# SparkFun_GPS_ZED-F9K.net
KiCad netlist of a schematic drawn in EAGLE
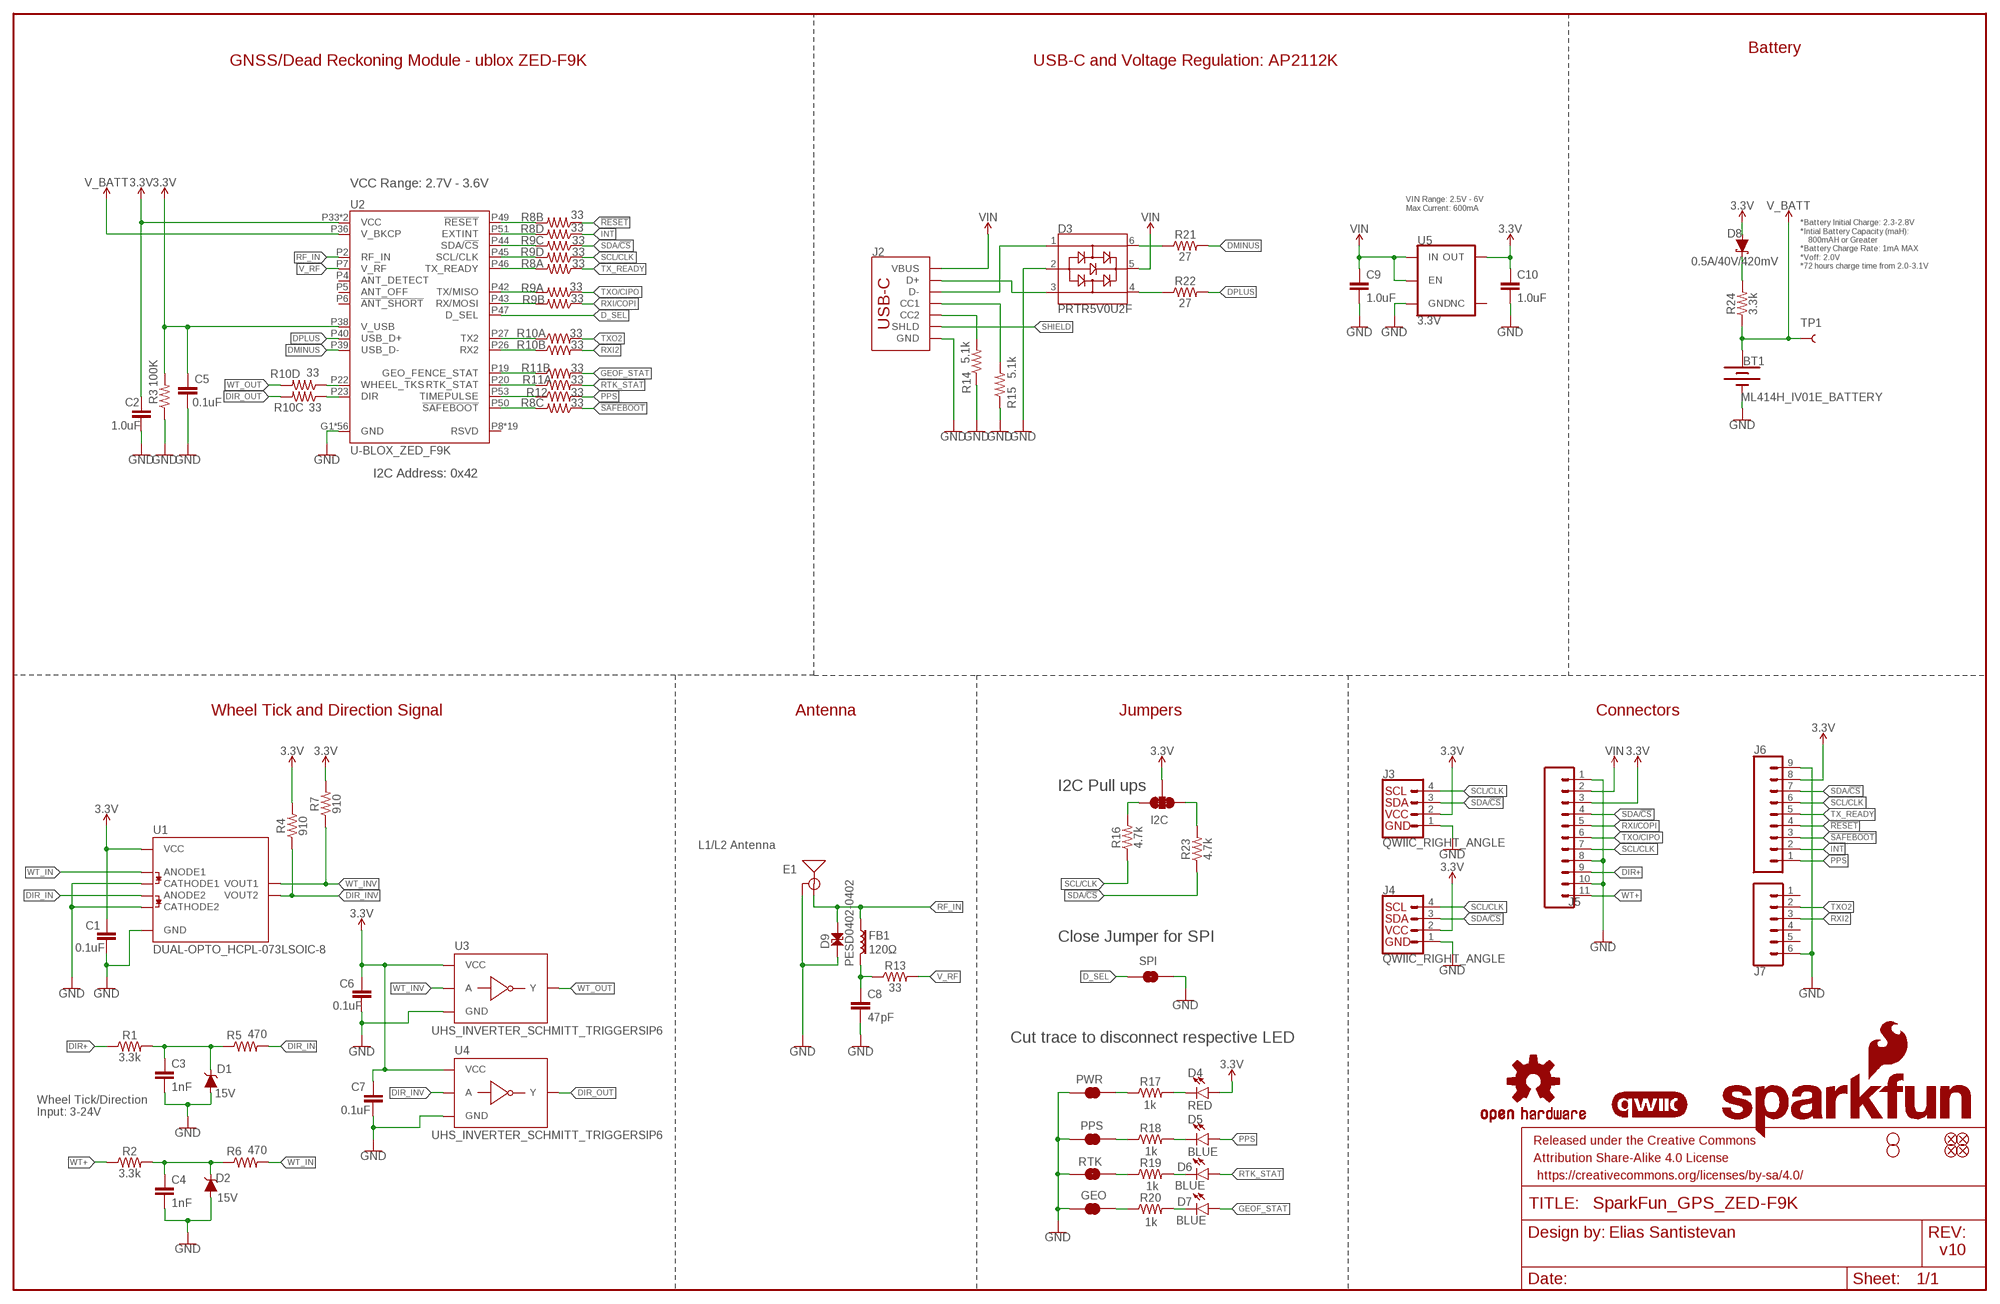
[diagram p0: schematic, sheet 1]

(export (version "E")
  (design (tool "Eeschema 10.0.6"))
  (components
    (comp (ref "$1_25_$_2020-03-30_22-52-05")
      (value "STAND-OFFTIGHT")
      (footprint "eagle-import:STAND-OFF-TIGHT")
      (libsource (lib "eagle-import") (part "STAND-OFFTIGHT"))
    )
    (comp (ref "BT1")
      (value "ML414H_IV01E_BATTERY")
      (footprint "eagle-import:ML414H_IV01E")
      (libsource (lib "eagle-import") (part "ML414H_IV01E_BATTERY"))
    )
    (comp (ref "C1")
      (value "0.1uF")
      (footprint "eagle-import:0402-TIGHT")
      (libsource (lib "eagle-import") (part "0.1UF-0402T-6.3V-10%-X7R"))
    )
    (comp (ref "C2")
      (value "1.0uF")
      (footprint "eagle-import:0402-TIGHT")
      (libsource (lib "eagle-import") (part "1.0UF-0402T-16V-10%"))
    )
    (comp (ref "C3")
      (value "1nF")
      (footprint "eagle-import:0402")
      (libsource (lib "eagle-import") (part "1.0NF/1000PF-0402-25V-10%-X7R"))
    )
    (comp (ref "C4")
      (value "1nF")
      (footprint "eagle-import:0402")
      (libsource (lib "eagle-import") (part "1.0NF/1000PF-0402-25V-10%-X7R"))
    )
    (comp (ref "C5")
      (value "0.1uF")
      (footprint "eagle-import:0402-TIGHT")
      (libsource (lib "eagle-import") (part "0.1UF-0402T-6.3V-10%-X7R"))
    )
    (comp (ref "C6")
      (value "0.1uF")
      (footprint "eagle-import:0402-TIGHT")
      (libsource (lib "eagle-import") (part "0.1UF-0402T-6.3V-10%-X7R"))
    )
    (comp (ref "C7")
      (value "0.1uF")
      (footprint "eagle-import:0402-TIGHT")
      (libsource (lib "eagle-import") (part "0.1UF-0402T-6.3V-10%-X7R"))
    )
    (comp (ref "C8")
      (value "47pF")
      (footprint "eagle-import:0402")
      (libsource (lib "eagle-import") (part "47PF-0402-25V-5%-X7R"))
    )
    (comp (ref "C9")
      (value "1.0uF")
      (footprint "eagle-import:0402-TIGHT")
      (libsource (lib "eagle-import") (part "1.0UF-0402T-16V-10%"))
    )
    (comp (ref "C10")
      (value "1.0uF")
      (footprint "eagle-import:0402-TIGHT")
      (libsource (lib "eagle-import") (part "1.0UF-0402T-16V-10%"))
    )
    (comp (ref "D1")
      (value "15V")
      (footprint "eagle-import:SOT23-3")
      (libsource (lib "eagle-import") (part "DIODE-ZENER-BZX84C15LT3G"))
    )
    (comp (ref "D2")
      (value "15V")
      (footprint "eagle-import:SOT23-3")
      (libsource (lib "eagle-import") (part "DIODE-ZENER-BZX84C15LT3G"))
    )
    (comp (ref "D3")
      (value "PRTR5V0U2F")
      (footprint "eagle-import:SOT886")
      (libsource (lib "eagle-import") (part "PRTR5V0U2F"))
    )
    (comp (ref "D4")
      (value "RED")
      (footprint "eagle-import:LED-0603")
      (libsource (lib "eagle-import") (part "LED-RED0603"))
    )
    (comp (ref "D5")
      (value "BLUE")
      (footprint "eagle-import:LED-0603")
      (libsource (lib "eagle-import") (part "LED-BLUE0603"))
    )
    (comp (ref "D6")
      (value "BLUE")
      (footprint "eagle-import:LED-0603")
      (libsource (lib "eagle-import") (part "LED-BLUE0603"))
    )
    (comp (ref "D7")
      (value "BLUE")
      (footprint "eagle-import:LED-0603")
      (libsource (lib "eagle-import") (part "LED-BLUE0603"))
    )
    (comp (ref "D8")
      (value "0.5A/40V/420mV")
      (footprint "eagle-import:SOD-323")
      (libsource (lib "eagle-import") (part "DIODE-SCHOTTKY-PMEG4005EJ"))
    )
    (comp (ref "D9")
      (value "PESD0402-0402")
      (footprint "eagle-import:0402")
      (fields
        (field (name "DIGIKEY_PART") "PESD0402-140CT-ND")
        (field (name "MOUSE_PART") "650-PESD0402-140")
      )
      (libsource (lib "eagle-import") (part "PESD0402-0402"))
    )
    (comp (ref "E1")
      (value "ANTENNA-SMA-GROUNDEDEDGE_SMA")
      (footprint "eagle-import:SMA-EDGE")
      (libsource (lib "eagle-import") (part "ANTENNA-SMA-GROUNDEDEDGE_SMA"))
    )
    (comp (ref "FB1")
      (value "120Ω")
      (footprint "eagle-import:0402")
      (fields (field (name "MFG_PART") "BLM15HB121SN1D"))
      (libsource (lib "eagle-import") (part "FERRITE_BEAD-120_OHM-0402"))
    )
    (comp (ref "FD1")
      (value "FIDUCIALUFIDUCIAL")
      (footprint "eagle-import:FIDUCIAL-MICRO")
      (libsource (lib "eagle-import") (part "FIDUCIALUFIDUCIAL"))
    )
    (comp (ref "FD2")
      (value "FIDUCIALUFIDUCIAL")
      (footprint "eagle-import:FIDUCIAL-MICRO")
      (libsource (lib "eagle-import") (part "FIDUCIALUFIDUCIAL"))
    )
    (comp (ref "FD3")
      (value "FIDUCIALUFIDUCIAL")
      (footprint "eagle-import:FIDUCIAL-MICRO")
      (libsource (lib "eagle-import") (part "FIDUCIALUFIDUCIAL"))
    )
    (comp (ref "FD4")
      (value "FIDUCIALUFIDUCIAL")
      (footprint "eagle-import:FIDUCIAL-MICRO")
      (libsource (lib "eagle-import") (part "FIDUCIALUFIDUCIAL"))
    )
    (comp (ref "FRAME1")
      (value "FRAME-LEDGER")
      (footprint "eagle-import:CREATIVE_COMMONS")
      (libsource (lib "eagle-import") (part "FRAME-LEDGER"))
    )
    (comp (ref "GEO")
      (value "JUMPER-SMT_2_NC_TRACE_SILK")
      (footprint "eagle-import:SMT-JUMPER_2_NC_TRACE_SILK")
      (libsource (lib "eagle-import") (part "JUMPER-SMT_2_NC_TRACE_SILK"))
    )
    (comp (ref "H2")
      (value "STAND-OFFTIGHT")
      (footprint "eagle-import:STAND-OFF-TIGHT")
      (libsource (lib "eagle-import") (part "STAND-OFFTIGHT"))
    )
    (comp (ref "I2C")
      (value "JUMPER-SMT_3_2-NC_TRACE_SILK")
      (footprint "eagle-import:SMT-JUMPER_3_2-NC_TRACE_SILK")
      (libsource (lib "eagle-import") (part "JUMPER-SMT_3_2-NC_TRACE_SILK"))
    )
    (comp (ref "J2")
      (value "USB_C_2-LAYER_PADS")
      (footprint "eagle-import:USB-C-16P-2LAYER-PADS")
      (libsource (lib "eagle-import") (part "USB_C_2-LAYER_PADS"))
    )
    (comp (ref "J3")
      (value "QWIIC_RIGHT_ANGLE")
      (footprint "eagle-import:JST04_1MM_RA")
      (libsource (lib "eagle-import") (part "QWIIC_CONNECTORJS-1MM"))
    )
    (comp (ref "J4")
      (value "QWIIC_RIGHT_ANGLE")
      (footprint "eagle-import:JST04_1MM_RA")
      (libsource (lib "eagle-import") (part "QWIIC_CONNECTORJS-1MM"))
    )
    (comp (ref "J5")
      (value "CONN_111X11_NO_SILK")
      (footprint "eagle-import:1X11_NO_SILK")
      (libsource (lib "eagle-import") (part "CONN_111X11_NO_SILK"))
    )
    (comp (ref "J6")
      (value "CONN_09NO_SILK")
      (footprint "eagle-import:1X09_NO_SILK")
      (libsource (lib "eagle-import") (part "CONN_09NO_SILK"))
    )
    (comp (ref "J7")
      (value "CONN_06NO_SILK_NO_POP")
      (footprint "eagle-import:1X06_NO_SILK")
      (libsource (lib "eagle-import") (part "CONN_06NO_SILK_NO_POP"))
    )
    (comp (ref "LOGO1")
      (value "OSHW-LOGOS")
      (footprint "eagle-import:OSHW-LOGO-S")
      (libsource (lib "eagle-import") (part "OSHW-LOGOS"))
    )
    (comp (ref "LOGO2")
      (value "QWIIC_LOGO_4MM")
      (footprint "eagle-import:QWIIC_4MM")
      (libsource (lib "eagle-import") (part "QWIIC_LOGO_4MM"))
    )
    (comp (ref "LOGO3")
      (value "SFE_LOGO_NAME_FLAME.2_INCH")
      (footprint "eagle-import:SFE_LOGO_NAME_FLAME_.2")
      (libsource (lib "eagle-import") (part "SFE_LOGO_NAME_FLAME.2_INCH"))
    )
    (comp (ref "PPS")
      (value "JUMPER-SMT_2_NC_TRACE_SILK")
      (footprint "eagle-import:SMT-JUMPER_2_NC_TRACE_SILK")
      (libsource (lib "eagle-import") (part "JUMPER-SMT_2_NC_TRACE_SILK"))
    )
    (comp (ref "PWR")
      (value "JUMPER-SMT_2_NC_TRACE_SILK")
      (footprint "eagle-import:SMT-JUMPER_2_NC_TRACE_SILK")
      (libsource (lib "eagle-import") (part "JUMPER-SMT_2_NC_TRACE_SILK"))
    )
    (comp (ref "R1")
      (value "3.3k")
      (footprint "eagle-import:0603")
      (libsource (lib "eagle-import") (part "3.3KOHM-0603-1/10W-1%"))
    )
    (comp (ref "R2")
      (value "3.3k")
      (footprint "eagle-import:0603")
      (libsource (lib "eagle-import") (part "3.3KOHM-0603-1/10W-1%"))
    )
    (comp (ref "R3")
      (value "100K")
      (footprint "eagle-import:0402")
      (libsource (lib "eagle-import") (part "100KOHM-0402-1/16W-1%"))
    )
    (comp (ref "R4")
      (value "910")
      (footprint "eagle-import:0603")
      (libsource (lib "eagle-import") (part "910OHM-0603-1/10W-5%"))
    )
    (comp (ref "R5")
      (value "470")
      (footprint "eagle-import:0603")
      (libsource (lib "eagle-import") (part "470OHM-0603-1/10W-1%"))
    )
    (comp (ref "R6")
      (value "470")
      (footprint "eagle-import:0603")
      (libsource (lib "eagle-import") (part "470OHM-0603-1/10W-1%"))
    )
    (comp (ref "R7")
      (value "910")
      (footprint "eagle-import:0603")
      (libsource (lib "eagle-import") (part "910OHM-0603-1/10W-5%"))
    )
    (comp (ref "R8")
      (value "33")
      (footprint "eagle-import:1206_RA")
      (libsource (lib "eagle-import") (part "33OHM_RA-1206-1/16W-5%"))
    )
    (comp (ref "R9")
      (value "33")
      (footprint "eagle-import:1206_RA")
      (libsource (lib "eagle-import") (part "33OHM_RA-1206-1/16W-5%"))
    )
    (comp (ref "R10")
      (value "33")
      (footprint "eagle-import:1206_RA")
      (libsource (lib "eagle-import") (part "33OHM_RA-1206-1/16W-5%"))
    )
    (comp (ref "R11")
      (value "33")
      (footprint "eagle-import:1206_RA")
      (libsource (lib "eagle-import") (part "33OHM_RA-1206-1/16W-5%"))
    )
    (comp (ref "R12")
      (value "33")
      (footprint "eagle-import:0603")
      (libsource (lib "eagle-import") (part "33OHM-0603-1/10W-1%"))
    )
    (comp (ref "R13")
      (value "33")
      (footprint "eagle-import:0603")
      (libsource (lib "eagle-import") (part "33OHM-0603-1/10W-1%"))
    )
    (comp (ref "R14")
      (value "5.1k")
      (footprint "eagle-import:0402")
      (libsource (lib "eagle-import") (part "5.1KOHM-0402-1/16W-1%"))
    )
    (comp (ref "R15")
      (value "5.1k")
      (footprint "eagle-import:0402")
      (libsource (lib "eagle-import") (part "5.1KOHM-0402-1/16W-1%"))
    )
    (comp (ref "R16")
      (value "4.7k")
      (footprint "eagle-import:0402-TIGHT")
      (libsource (lib "eagle-import") (part "4.7KOHM-0402T-1/16W-1%"))
    )
    (comp (ref "R17")
      (value "1KOHM-0402-1/16W-1%")
      (footprint "eagle-import:0402")
      (libsource (lib "eagle-import") (part "1KOHM-0402-1/16W-1%"))
    )
    (comp (ref "R18")
      (value "1KOHM-0402-1/16W-1%")
      (footprint "eagle-import:0402")
      (libsource (lib "eagle-import") (part "1KOHM-0402-1/16W-1%"))
    )
    (comp (ref "R19")
      (value "1KOHM-0402-1/16W-1%")
      (footprint "eagle-import:0402")
      (libsource (lib "eagle-import") (part "1KOHM-0402-1/16W-1%"))
    )
    (comp (ref "R20")
      (value "1KOHM-0402-1/16W-1%")
      (footprint "eagle-import:0402")
      (libsource (lib "eagle-import") (part "1KOHM-0402-1/16W-1%"))
    )
    (comp (ref "R21")
      (value "27")
      (footprint "eagle-import:0603")
      (libsource (lib "eagle-import") (part "27OHM-0603-1/10W-1%"))
    )
    (comp (ref "R22")
      (value "27")
      (footprint "eagle-import:0603")
      (libsource (lib "eagle-import") (part "27OHM-0603-1/10W-1%"))
    )
    (comp (ref "R23")
      (value "4.7k")
      (footprint "eagle-import:0402-TIGHT")
      (libsource (lib "eagle-import") (part "4.7KOHM-0402T-1/16W-1%"))
    )
    (comp (ref "R24")
      (value "3.3k")
      (footprint "eagle-import:0603")
      (libsource (lib "eagle-import") (part "3.3KOHM-0603-1/10W-1%"))
    )
    (comp (ref "RTK")
      (value "JUMPER-SMT_2_NC_TRACE_SILK")
      (footprint "eagle-import:SMT-JUMPER_2_NC_TRACE_SILK")
      (libsource (lib "eagle-import") (part "JUMPER-SMT_2_NC_TRACE_SILK"))
    )
    (comp (ref "SPI")
      (value "JUMPER-SMT_2_NO_SILK")
      (footprint "eagle-import:SMT-JUMPER_2_NO_SILK")
      (libsource (lib "eagle-import") (part "JUMPER-SMT_2_NO_SILK"))
    )
    (comp (ref "TP1")
      (value "TEST-POINT3X5")
      (footprint "eagle-import:PAD.03X.05")
      (libsource (lib "eagle-import") (part "TEST-POINT3X5"))
    )
    (comp (ref "U1")
      (value "DUAL-OPTO_HCPL-073LSOIC-8")
      (footprint "eagle-import:SO08")
      (libsource (lib "eagle-import") (part "DUAL-OPTO_HCPL-073LSOIC-8"))
    )
    (comp (ref "U2")
      (value "U-BLOX_ZED_F9K")
      (footprint "eagle-import:UBLOX_ZED_F9K")
      (libsource (lib "eagle-import") (part "U-BLOX_ZED_F9K"))
    )
    (comp (ref "U3")
      (value "UHS_INVERTER_SCHMITT_TRIGGERSIP6")
      (footprint "eagle-import:SIP6")
      (libsource (lib "eagle-import") (part "UHS_INVERTER_SCHMITT_TRIGGERSIP6"))
    )
    (comp (ref "U4")
      (value "UHS_INVERTER_SCHMITT_TRIGGERSIP6")
      (footprint "eagle-import:SIP6")
      (libsource (lib "eagle-import") (part "UHS_INVERTER_SCHMITT_TRIGGERSIP6"))
    )
    (comp (ref "U5")
      (value "3.3V")
      (footprint "eagle-import:SOT23-5")
      (libsource (lib "eagle-import") (part "V_REG_AP2112K-3.3V"))
    )
  )
  (nets
    (net (code "1") (name "/SDA{slash}~{CS}") (class "Default")
      (node (ref "J3") (pin "3") (pinfunction "3_3") (pintype "passive"))
      (node (ref "J4") (pin "3") (pinfunction "3_3") (pintype "passive"))
      (node (ref "J5") (pin "4") (pinfunction "4_4") (pintype "passive"))
      (node (ref "J6") (pin "7") (pinfunction "7_7") (pintype "passive"))
      (node (ref "R23") (pin "1") (pinfunction "1_1") (pintype "passive"))
      (node (ref "R9") (pin "P3") (pinfunction "1_P3") (pintype "passive"))
    )
    (net (code "2") (name "/~{RESET}") (class "Default")
      (node (ref "J6") (pin "4") (pinfunction "4_4") (pintype "passive"))
      (node (ref "R8") (pin "P2") (pinfunction "1_P2") (pintype "passive"))
    )
    (net (code "3") (name "/~{SAFEBOOT}") (class "Default")
      (node (ref "J6") (pin "3") (pinfunction "3_3") (pintype "passive"))
      (node (ref "R8") (pin "P3") (pinfunction "1_P3") (pintype "passive"))
    )
    (net (code "4") (name "3.3V") (class "Default")
      (node (ref "C1") (pin "1") (pinfunction "1_1") (pintype "passive"))
      (node (ref "C10") (pin "1") (pinfunction "1_1") (pintype "passive"))
      (node (ref "C2") (pin "1") (pinfunction "1_1") (pintype "passive"))
      (node (ref "C5") (pin "1") (pinfunction "1_1") (pintype "passive"))
      (node (ref "C6") (pin "1") (pinfunction "1_1") (pintype "passive"))
      (node (ref "C7") (pin "1") (pinfunction "1_1") (pintype "passive"))
      (node (ref "D4") (pin "A") (pinfunction "A_A") (pintype "passive"))
      (node (ref "D8") (pin "A") (pinfunction "A_A") (pintype "passive"))
      (node (ref "I2C") (pin "2") (pinfunction "2_2") (pintype "passive"))
      (node (ref "J3") (pin "2") (pinfunction "2_2") (pintype "power_in"))
      (node (ref "J4") (pin "2") (pinfunction "2_2") (pintype "power_in"))
      (node (ref "J5") (pin "3") (pinfunction "3_3") (pintype "passive"))
      (node (ref "J6") (pin "8") (pinfunction "8_8") (pintype "passive"))
      (node (ref "R3") (pin "2") (pinfunction "2_2") (pintype "passive"))
      (node (ref "R4") (pin "2") (pinfunction "2_2") (pintype "passive"))
      (node (ref "R7") (pin "2") (pinfunction "2_2") (pintype "passive"))
      (node (ref "U1") (pin "8") (pinfunction "VCC_8") (pintype "power_in"))
      (node (ref "U2") (pin "P33") (pinfunction "VCC_P33") (pintype "power_in"))
      (node (ref "U2") (pin "P34") (pinfunction "VCC_P34") (pintype "power_in"))
      (node (ref "U2") (pin "P38") (pinfunction "V_USB_P38") (pintype "power_in"))
      (node (ref "U3") (pin "P6") (pinfunction "VCC_P6") (pintype "power_in"))
      (node (ref "U4") (pin "P6") (pinfunction "VCC_P6") (pintype "power_in"))
      (node (ref "U5") (pin "5") (pinfunction "OUT_5") (pintype "passive"))
    )
    (net (code "5") (name "DIR+") (class "Default")
      (node (ref "J5") (pin "9") (pinfunction "9_9") (pintype "passive"))
      (node (ref "R1") (pin "1") (pinfunction "1_1") (pintype "passive"))
    )
    (net (code "6") (name "DIR_IN") (class "Default")
      (node (ref "R5") (pin "2") (pinfunction "2_2") (pintype "passive"))
      (node (ref "U1") (pin "4") (pinfunction "ANODE2_4") (pintype "input"))
    )
    (net (code "7") (name "DIR_INV") (class "Default")
      (node (ref "R4") (pin "1") (pinfunction "1_1") (pintype "passive"))
      (node (ref "U1") (pin "6") (pinfunction "VOUT2_6") (pintype "output"))
      (node (ref "U4") (pin "P2") (pinfunction "A_P2") (pintype "input"))
    )
    (net (code "8") (name "DIR_OUT") (class "Default")
      (node (ref "R10") (pin "P6") (pinfunction "2_P6") (pintype "passive"))
      (node (ref "U4") (pin "P4") (pinfunction "Y_P4") (pintype "output"))
    )
    (net (code "9") (name "DMINUS") (class "Default")
      (node (ref "R21") (pin "2") (pinfunction "2_2") (pintype "passive"))
      (node (ref "U2") (pin "P39") (pinfunction "USB_D-_P39") (pintype "bidirectional"))
    )
    (net (code "10") (name "DPLUS") (class "Default")
      (node (ref "R22") (pin "2") (pinfunction "2_2") (pintype "passive"))
      (node (ref "U2") (pin "P40") (pinfunction "USB_D+_P40") (pintype "bidirectional"))
    )
    (net (code "11") (name "D_SEL") (class "Default")
      (node (ref "SPI") (pin "1") (pinfunction "1_1") (pintype "passive"))
      (node (ref "U2") (pin "P47") (pinfunction "D_SEL_P47") (pintype "bidirectional"))
    )
    (net (code "12") (name "GEOF_STAT") (class "Default")
      (node (ref "D7") (pin "A") (pinfunction "A_A") (pintype "passive"))
      (node (ref "R11") (pin "P7") (pinfunction "2_P7") (pintype "passive"))
    )
    (net (code "13") (name "GND") (class "Default")
      (node (ref "BT1") (pin "-") (pinfunction "-_-") (pintype "power_in"))
      (node (ref "C1") (pin "2") (pinfunction "2_2") (pintype "passive"))
      (node (ref "C10") (pin "2") (pinfunction "2_2") (pintype "passive"))
      (node (ref "C2") (pin "2") (pinfunction "2_2") (pintype "passive"))
      (node (ref "C3") (pin "2") (pinfunction "2_2") (pintype "passive"))
      (node (ref "C4") (pin "2") (pinfunction "2_2") (pintype "passive"))
      (node (ref "C5") (pin "2") (pinfunction "2_2") (pintype "passive"))
      (node (ref "C6") (pin "2") (pinfunction "2_2") (pintype "passive"))
      (node (ref "C7") (pin "2") (pinfunction "2_2") (pintype "passive"))
      (node (ref "C8") (pin "2") (pinfunction "2_2") (pintype "passive"))
      (node (ref "C9") (pin "2") (pinfunction "2_2") (pintype "passive"))
      (node (ref "D1") (pin "1") (pinfunction "A_1") (pintype "passive"))
      (node (ref "D2") (pin "1") (pinfunction "A_1") (pintype "passive"))
      (node (ref "D3") (pin "2") (pinfunction "2_2") (pintype "power_in"))
      (node (ref "D9") (pin "1") (pinfunction "1_1") (pintype "bidirectional"))
      (node (ref "E1") (pin "GND@0") (pinfunction "GND_GND@0") (pintype "bidirectional"))
      (node (ref "E1") (pin "GND@1") (pinfunction "GND_GND@1") (pintype "bidirectional"))
      (node (ref "E1") (pin "GND@2") (pinfunction "GND_GND@2") (pintype "bidirectional"))
      (node (ref "E1") (pin "GND@3") (pinfunction "GND_GND@3") (pintype "bidirectional"))
      (node (ref "GEO") (pin "1") (pinfunction "1_1") (pintype "passive"))
      (node (ref "J2") (pin "GND") (pinfunction "GND_GND") (pintype "bidirectional"))
      (node (ref "J2") (pin "GND2") (pinfunction "GND_GND2") (pintype "bidirectional"))
      (node (ref "J3") (pin "1") (pinfunction "1_1") (pintype "power_in"))
      (node (ref "J4") (pin "1") (pinfunction "1_1") (pintype "power_in"))
      (node (ref "J5") (pin "1") (pinfunction "1_1") (pintype "passive"))
      (node (ref "J5") (pin "10") (pinfunction "10_10") (pintype "passive"))
      (node (ref "J5") (pin "8") (pinfunction "8_8") (pintype "passive"))
      (node (ref "J6") (pin "9") (pinfunction "9_9") (pintype "passive"))
      (node (ref "J7") (pin "6") (pinfunction "6_6") (pintype "passive"))
      (node (ref "PPS") (pin "1") (pinfunction "1_1") (pintype "passive"))
      (node (ref "PWR") (pin "1") (pinfunction "1_1") (pintype "passive"))
      (node (ref "R14") (pin "1") (pinfunction "1_1") (pintype "passive"))
      (node (ref "R15") (pin "1") (pinfunction "1_1") (pintype "passive"))
      (node (ref "R3") (pin "1") (pinfunction "1_1") (pintype "passive"))
      (node (ref "RTK") (pin "1") (pinfunction "1_1") (pintype "passive"))
      (node (ref "SPI") (pin "2") (pinfunction "2_2") (pintype "passive"))
      (node (ref "U1") (pin "2") (pinfunction "CATHODE1_2") (pintype "input"))
      (node (ref "U1") (pin "3") (pinfunction "CATHODE2_3") (pintype "input"))
      (node (ref "U1") (pin "5") (pinfunction "GND_5") (pintype "power_in"))
      (node (ref "U2") (pin "G1") (pinfunction "GND_G1") (pintype "power_in"))
      (node (ref "U2") (pin "G10") (pinfunction "GND_G10") (pintype "power_in"))
      (node (ref "U2") (pin "G11") (pinfunction "GND_G11") (pintype "power_in"))
      (node (ref "U2") (pin "G12") (pinfunction "GND_G12") (pintype "power_in"))
      (node (ref "U2") (pin "G13") (pinfunction "GND_G13") (pintype "power_in"))
      (node (ref "U2") (pin "G14") (pinfunction "GND_G14") (pintype "power_in"))
      (node (ref "U2") (pin "G15") (pinfunction "GND_G15") (pintype "power_in"))
      (node (ref "U2") (pin "G16") (pinfunction "GND_G16") (pintype "power_in"))
      (node (ref "U2") (pin "G17") (pinfunction "GND_G17") (pintype "power_in"))
      (node (ref "U2") (pin "G18") (pinfunction "GND_G18") (pintype "power_in"))
      (node (ref "U2") (pin "G19") (pinfunction "GND_G19") (pintype "power_in"))
      (node (ref "U2") (pin "G2") (pinfunction "GND_G2") (pintype "power_in"))
      (node (ref "U2") (pin "G20") (pinfunction "GND_G20") (pintype "power_in"))
      (node (ref "U2") (pin "G21") (pinfunction "GND_G21") (pintype "power_in"))
      (node (ref "U2") (pin "G22") (pinfunction "GND_G22") (pintype "power_in"))
      (node (ref "U2") (pin "G23") (pinfunction "GND_G23") (pintype "power_in"))
      (node (ref "U2") (pin "G24") (pinfunction "GND_G24") (pintype "power_in"))
      (node (ref "U2") (pin "G25") (pinfunction "GND_G25") (pintype "power_in"))
      (node (ref "U2") (pin "G26") (pinfunction "GND_G26") (pintype "power_in"))
      (node (ref "U2") (pin "G27") (pinfunction "GND_G27") (pintype "power_in"))
      (node (ref "U2") (pin "G28") (pinfunction "GND_G28") (pintype "power_in"))
      (node (ref "U2") (pin "G29") (pinfunction "GND_G29") (pintype "power_in"))
      (node (ref "U2") (pin "G3") (pinfunction "GND_G3") (pintype "power_in"))
      (node (ref "U2") (pin "G30") (pinfunction "GND_G30") (pintype "power_in"))
      (node (ref "U2") (pin "G31") (pinfunction "GND_G31") (pintype "power_in"))
      (node (ref "U2") (pin "G32") (pinfunction "GND_G32") (pintype "power_in"))
      (node (ref "U2") (pin "G33") (pinfunction "GND_G33") (pintype "power_in"))
      (node (ref "U2") (pin "G34") (pinfunction "GND_G34") (pintype "power_in"))
      (node (ref "U2") (pin "G35") (pinfunction "GND_G35") (pintype "power_in"))
      (node (ref "U2") (pin "G36") (pinfunction "GND_G36") (pintype "power_in"))
      (node (ref "U2") (pin "G37") (pinfunction "GND_G37") (pintype "power_in"))
      (node (ref "U2") (pin "G38") (pinfunction "GND_G38") (pintype "power_in"))
      (node (ref "U2") (pin "G39") (pinfunction "GND_G39") (pintype "power_in"))
      (node (ref "U2") (pin "G4") (pinfunction "GND_G4") (pintype "power_in"))
      (node (ref "U2") (pin "G40") (pinfunction "GND_G40") (pintype "power_in"))
      (node (ref "U2") (pin "G41") (pinfunction "GND_G41") (pintype "power_in"))
      (node (ref "U2") (pin "G42") (pinfunction "GND_G42") (pintype "power_in"))
      (node (ref "U2") (pin "G43") (pinfunction "GND_G43") (pintype "power_in"))
      (node (ref "U2") (pin "G44") (pinfunction "GND_G44") (pintype "power_in"))
      (node (ref "U2") (pin "G45") (pinfunction "GND_G45") (pintype "power_in"))
      (node (ref "U2") (pin "G46") (pinfunction "GND_G46") (pintype "power_in"))
      (node (ref "U2") (pin "G47") (pinfunction "GND_G47") (pintype "power_in"))
      (node (ref "U2") (pin "G48") (pinfunction "GND_G48") (pintype "power_in"))
      (node (ref "U2") (pin "G5") (pinfunction "GND_G5") (pintype "power_in"))
      (node (ref "U2") (pin "G6") (pinfunction "GND_G6") (pintype "power_in"))
      (node (ref "U2") (pin "G7") (pinfunction "GND_G7") (pintype "power_in"))
      (node (ref "U2") (pin "G8") (pinfunction "GND_G8") (pintype "power_in"))
      (node (ref "U2") (pin "G9") (pinfunction "GND_G9") (pintype "power_in"))
      (node (ref "U2") (pin "P1") (pinfunction "GND_P1") (pintype "power_in"))
      (node (ref "U2") (pin "P12") (pinfunction "GND_P12") (pintype "power_in"))
      (node (ref "U2") (pin "P14") (pinfunction "GND_P14") (pintype "power_in"))
      (node (ref "U2") (pin "P3") (pinfunction "GND_P3") (pintype "power_in"))
      (node (ref "U2") (pin "P32") (pinfunction "GND_P32") (pintype "power_in"))
      (node (ref "U2") (pin "P37") (pinfunction "GND_P37") (pintype "power_in"))
      (node (ref "U2") (pin "P41") (pinfunction "GND_P41") (pintype "power_in"))
      (node (ref "U2") (pin "P48") (pinfunction "GND_P48") (pintype "power_in"))
      (node (ref "U3") (pin "P3") (pinfunction "GND_P3") (pintype "power_in"))
      (node (ref "U4") (pin "P3") (pinfunction "GND_P3") (pintype "power_in"))
      (node (ref "U5") (pin "2") (pinfunction "GND_2") (pintype "input"))
    )
    (net (code "14") (name "INT") (class "Default")
      (node (ref "J6") (pin "2") (pinfunction "2_2") (pintype "passive"))
      (node (ref "R8") (pin "P4") (pinfunction "1_P4") (pintype "passive"))
    )
    (net (code "15") (name "Net-(C8-Pad1)") (class "Default")
      (node (ref "C8") (pin "1") (pinfunction "1_1") (pintype "passive"))
      (node (ref "FB1") (pin "2") (pinfunction "2_2") (pintype "passive"))
      (node (ref "R13") (pin "1") (pinfunction "1_1") (pintype "passive"))
    )
    (net (code "16") (name "Net-(D1-C)") (class "Default")
      (node (ref "C3") (pin "1") (pinfunction "1_1") (pintype "passive"))
      (node (ref "D1") (pin "3") (pinfunction "C_3") (pintype "passive"))
      (node (ref "R1") (pin "2") (pinfunction "2_2") (pintype "passive"))
      (node (ref "R5") (pin "1") (pinfunction "1_1") (pintype "passive"))
    )
    (net (code "17") (name "Net-(D2-C)") (class "Default")
      (node (ref "C4") (pin "1") (pinfunction "1_1") (pintype "passive"))
      (node (ref "D2") (pin "3") (pinfunction "C_3") (pintype "passive"))
      (node (ref "R2") (pin "2") (pinfunction "2_2") (pintype "passive"))
      (node (ref "R6") (pin "1") (pinfunction "1_1") (pintype "passive"))
    )
    (net (code "18") (name "Net-(D3-Pad1)") (class "Default")
      (node (ref "D3") (pin "1") (pinfunction "1_1") (pintype "bidirectional"))
      (node (ref "J2") (pin "A7") (pinfunction "D-_A7") (pintype "bidirectional"))
      (node (ref "J2") (pin "B7") (pinfunction "D-_B7") (pintype "bidirectional"))
    )
    (net (code "19") (name "Net-(D3-Pad3)") (class "Default")
      (node (ref "D3") (pin "3") (pinfunction "3_3") (pintype "bidirectional"))
      (node (ref "J2") (pin "A6") (pinfunction "D+_A6") (pintype "bidirectional"))
      (node (ref "J2") (pin "B6") (pinfunction "D+_B6") (pintype "bidirectional"))
    )
    (net (code "20") (name "Net-(D3-Pad4)") (class "Default")
      (node (ref "D3") (pin "4") (pinfunction "4_4") (pintype "bidirectional"))
      (node (ref "R22") (pin "1") (pinfunction "1_1") (pintype "passive"))
    )
    (net (code "21") (name "Net-(D3-Pad6)") (class "Default")
      (node (ref "D3") (pin "6") (pinfunction "6_6") (pintype "bidirectional"))
      (node (ref "R21") (pin "1") (pinfunction "1_1") (pintype "passive"))
    )
    (net (code "22") (name "Net-(D4-PadC)") (class "Default")
      (node (ref "D4") (pin "C") (pinfunction "C_C") (pintype "passive"))
      (node (ref "R17") (pin "2") (pinfunction "2_2") (pintype "passive"))
    )
    (net (code "23") (name "Net-(D5-PadC)") (class "Default")
      (node (ref "D5") (pin "C") (pinfunction "C_C") (pintype "passive"))
      (node (ref "R18") (pin "2") (pinfunction "2_2") (pintype "passive"))
    )
    (net (code "24") (name "Net-(D6-PadC)") (class "Default")
      (node (ref "D6") (pin "C") (pinfunction "C_C") (pintype "passive"))
      (node (ref "R19") (pin "2") (pinfunction "2_2") (pintype "passive"))
    )
    (net (code "25") (name "Net-(D7-PadC)") (class "Default")
      (node (ref "D7") (pin "C") (pinfunction "C_C") (pintype "passive"))
      (node (ref "R20") (pin "2") (pinfunction "2_2") (pintype "passive"))
    )
    (net (code "26") (name "Net-(D8-PadC)") (class "Default")
      (node (ref "D8") (pin "C") (pinfunction "C_C") (pintype "passive"))
      (node (ref "R24") (pin "2") (pinfunction "2_2") (pintype "passive"))
    )
    (net (code "27") (name "Net-(GEO-Pad2)") (class "Default")
      (node (ref "GEO") (pin "2") (pinfunction "2_2") (pintype "passive"))
      (node (ref "R20") (pin "1") (pinfunction "1_1") (pintype "passive"))
    )
    (net (code "28") (name "Net-(I2C-Pad1)") (class "Default")
      (node (ref "I2C") (pin "1") (pinfunction "1_1") (pintype "passive"))
      (node (ref "R23") (pin "2") (pinfunction "2_2") (pintype "passive"))
    )
    (net (code "29") (name "Net-(I2C-Pad3)") (class "Default")
      (node (ref "I2C") (pin "3") (pinfunction "3_3") (pintype "passive"))
      (node (ref "R16") (pin "2") (pinfunction "2_2") (pintype "passive"))
    )
    (net (code "30") (name "Net-(J2-CC1)") (class "Default")
      (node (ref "J2") (pin "A5") (pinfunction "CC1_A5") (pintype "bidirectional"))
      (node (ref "R15") (pin "2") (pinfunction "2_2") (pintype "passive"))
    )
    (net (code "31") (name "Net-(J2-CC2)") (class "Default")
      (node (ref "J2") (pin "B5") (pinfunction "CC2_B5") (pintype "bidirectional"))
      (node (ref "R14") (pin "2") (pinfunction "2_2") (pintype "passive"))
    )
    (net (code "32") (name "Net-(PPS-Pad2)") (class "Default")
      (node (ref "PPS") (pin "2") (pinfunction "2_2") (pintype "passive"))
      (node (ref "R18") (pin "1") (pinfunction "1_1") (pintype "passive"))
    )
    (net (code "33") (name "Net-(PWR-Pad2)") (class "Default")
      (node (ref "PWR") (pin "2") (pinfunction "2_2") (pintype "passive"))
      (node (ref "R17") (pin "1") (pinfunction "1_1") (pintype "passive"))
    )
    (net (code "34") (name "Net-(R8A-2)") (class "Default")
      (node (ref "R8") (pin "P8") (pinfunction "2_P8") (pintype "passive"))
      (node (ref "U2") (pin "P46") (pinfunction "TX_READY_P46") (pintype "bidirectional"))
    )
    (net (code "35") (name "Net-(R8B-2)") (class "Default")
      (node (ref "R8") (pin "P7") (pinfunction "2_P7") (pintype "passive"))
      (node (ref "U2") (pin "P49") (pinfunction "~{RESET}_P49") (pintype "bidirectional"))
    )
    (net (code "36") (name "Net-(R8C-2)") (class "Default")
      (node (ref "R8") (pin "P6") (pinfunction "2_P6") (pintype "passive"))
      (node (ref "U2") (pin "P50") (pinfunction "~{SAFEBOOT}_P50") (pintype "input"))
    )
    (net (code "37") (name "Net-(R8D-2)") (class "Default")
      (node (ref "R8") (pin "P5") (pinfunction "2_P5") (pintype "passive"))
      (node (ref "U2") (pin "P51") (pinfunction "EXTINT_P51") (pintype "bidirectional"))
    )
    (net (code "38") (name "Net-(R9A-2)") (class "Default")
      (node (ref "R9") (pin "P8") (pinfunction "2_P8") (pintype "passive"))
      (node (ref "U2") (pin "P42") (pinfunction "TX/MISO_P42") (pintype "bidirectional"))
    )
    (net (code "39") (name "Net-(R9B-2)") (class "Default")
      (node (ref "R9") (pin "P7") (pinfunction "2_P7") (pintype "passive"))
      (node (ref "U2") (pin "P43") (pinfunction "RX/MOSI_P43") (pintype "bidirectional"))
    )
    (net (code "40") (name "Net-(R9C-2)") (class "Default")
      (node (ref "R9") (pin "P6") (pinfunction "2_P6") (pintype "passive"))
      (node (ref "U2") (pin "P44") (pinfunction "SDA/~{CS}_P44") (pintype "bidirectional"))
    )
    (net (code "41") (name "Net-(R9D-2)") (class "Default")
      (node (ref "R9") (pin "P5") (pinfunction "2_P5") (pintype "passive"))
      (node (ref "U2") (pin "P45") (pinfunction "SCL/CLK_P45") (pintype "bidirectional"))
    )
    (net (code "42") (name "Net-(R10A-1)") (class "Default")
      (node (ref "R10") (pin "P1") (pinfunction "1_P1") (pintype "passive"))
      (node (ref "U2") (pin "P27") (pinfunction "TX2_P27") (pintype "output"))
    )
    (net (code "43") (name "Net-(R10B-1)") (class "Default")
      (node (ref "R10") (pin "P2") (pinfunction "1_P2") (pintype "passive"))
      (node (ref "U2") (pin "P26") (pinfunction "RX2_P26") (pintype "input"))
    )
    (net (code "44") (name "Net-(R10C-1)") (class "Default")
      (node (ref "R10") (pin "P3") (pinfunction "1_P3") (pintype "passive"))
      (node (ref "U2") (pin "P23") (pinfunction "DIR_P23") (pintype "input"))
    )
    (net (code "45") (name "Net-(R10D-1)") (class "Default")
      (node (ref "R10") (pin "P4") (pinfunction "1_P4") (pintype "passive"))
      (node (ref "U2") (pin "P22") (pinfunction "WHEEL_TKS_P22") (pintype "input"))
    )
    (net (code "46") (name "Net-(R11A-1)") (class "Default")
      (node (ref "R11") (pin "P1") (pinfunction "1_P1") (pintype "passive"))
      (node (ref "U2") (pin "P20") (pinfunction "RTK_STAT_P20") (pintype "output"))
    )
    (net (code "47") (name "Net-(R11B-1)") (class "Default")
      (node (ref "R11") (pin "P2") (pinfunction "1_P2") (pintype "passive"))
      (node (ref "U2") (pin "P19") (pinfunction "GEO_FENCE_STAT_P19") (pintype "output"))
    )
    (net (code "48") (name "Net-(R19-Pad1)") (class "Default")
      (node (ref "R19") (pin "1") (pinfunction "1_1") (pintype "passive"))
      (node (ref "RTK") (pin "2") (pinfunction "2_2") (pintype "passive"))
    )
    (net (code "49") (name "Net-(U2-TIMEPULSE)") (class "Default")
      (node (ref "R12") (pin "1") (pinfunction "1_1") (pintype "passive"))
      (node (ref "U2") (pin "P53") (pinfunction "TIMEPULSE_P53") (pintype "output"))
    )
    (net (code "50") (name "PPS") (class "Default")
      (node (ref "D5") (pin "A") (pinfunction "A_A") (pintype "passive"))
      (node (ref "J6") (pin "1") (pinfunction "1_1") (pintype "passive"))
      (node (ref "R12") (pin "2") (pinfunction "2_2") (pintype "passive"))
    )
    (net (code "51") (name "RF_IN") (class "Default")
      (node (ref "D9") (pin "2") (pinfunction "2_2") (pintype "bidirectional"))
      (node (ref "E1") (pin "SIG") (pinfunction "SIGNAL_SIG") (pintype "bidirectional"))
      (node (ref "FB1") (pin "1") (pinfunction "1_1") (pintype "passive"))
      (node (ref "U2") (pin "P2") (pinfunction "RF_IN_P2") (pintype "input"))
    )
    (net (code "52") (name "RTK_STAT") (class "Default")
      (node (ref "D6") (pin "A") (pinfunction "A_A") (pintype "passive"))
      (node (ref "R11") (pin "P8") (pinfunction "2_P8") (pintype "passive"))
    )
    (net (code "53") (name "RXI2") (class "Default")
      (node (ref "J7") (pin "3") (pinfunction "3_3") (pintype "passive"))
      (node (ref "R10") (pin "P7") (pinfunction "2_P7") (pintype "passive"))
    )
    (net (code "54") (name "RXI{slash}COPI") (class "Default")
      (node (ref "J5") (pin "5") (pinfunction "5_5") (pintype "passive"))
      (node (ref "R9") (pin "P2") (pinfunction "1_P2") (pintype "passive"))
    )
    (net (code "55") (name "SCL{slash}CLK") (class "Default")
      (node (ref "J3") (pin "4") (pinfunction "4_4") (pintype "passive"))
      (node (ref "J4") (pin "4") (pinfunction "4_4") (pintype "passive"))
      (node (ref "J5") (pin "7") (pinfunction "7_7") (pintype "passive"))
      (node (ref "J6") (pin "6") (pinfunction "6_6") (pintype "passive"))
      (node (ref "R16") (pin "1") (pinfunction "1_1") (pintype "passive"))
      (node (ref "R9") (pin "P4") (pinfunction "1_P4") (pintype "passive"))
    )
    (net (code "56") (name "SHIELD") (class "Default")
      (node (ref "J2") (pin "SHLD1") (pinfunction "SHLD_SHLD1") (pintype "bidirectional"))
      (node (ref "J2") (pin "SHLD2") (pinfunction "SHLD_SHLD2") (pintype "bidirectional"))
      (node (ref "J2") (pin "SHLD3") (pinfunction "SHLD_SHLD3") (pintype "bidirectional"))
      (node (ref "J2") (pin "SHLD4") (pinfunction "SHLD_SHLD4") (pintype "bidirectional"))
    )
    (net (code "57") (name "TXO2") (class "Default")
      (node (ref "J7") (pin "2") (pinfunction "2_2") (pintype "passive"))
      (node (ref "R10") (pin "P8") (pinfunction "2_P8") (pintype "passive"))
    )
    (net (code "58") (name "TXO{slash}CIPO") (class "Default")
      (node (ref "J5") (pin "6") (pinfunction "6_6") (pintype "passive"))
      (node (ref "R9") (pin "P1") (pinfunction "1_P1") (pintype "passive"))
    )
    (net (code "59") (name "TX_READY") (class "Default")
      (node (ref "J6") (pin "5") (pinfunction "5_5") (pintype "passive"))
      (node (ref "R8") (pin "P1") (pinfunction "1_P1") (pintype "passive"))
    )
    (net (code "60") (name "VIN") (class "Default")
      (node (ref "C9") (pin "1") (pinfunction "1_1") (pintype "passive"))
      (node (ref "D3") (pin "5") (pinfunction "5_5") (pintype "power_in"))
      (node (ref "J2") (pin "VBUS1") (pinfunction "VBUS_VBUS1") (pintype "bidirectional"))
      (node (ref "J2") (pin "VBUS2") (pinfunction "VBUS_VBUS2") (pintype "bidirectional"))
      (node (ref "J5") (pin "2") (pinfunction "2_2") (pintype "passive"))
      (node (ref "U5") (pin "1") (pinfunction "IN_1") (pintype "input"))
      (node (ref "U5") (pin "3") (pinfunction "EN_3") (pintype "input"))
    )
    (net (code "61") (name "V_BATT") (class "Default")
      (node (ref "BT1") (pin "+") (pinfunction "+_+") (pintype "power_in"))
      (node (ref "R24") (pin "1") (pinfunction "1_1") (pintype "passive"))
      (node (ref "TP1") (pin "1") (pinfunction "1_1") (pintype "bidirectional"))
      (node (ref "U2") (pin "P36") (pinfunction "V_BKCP_P36") (pintype "power_in"))
    )
    (net (code "62") (name "V_RF") (class "Default")
      (node (ref "R13") (pin "2") (pinfunction "2_2") (pintype "passive"))
      (node (ref "U2") (pin "P7") (pinfunction "V_RF_P7") (pintype "output"))
    )
    (net (code "63") (name "WT+") (class "Default")
      (node (ref "J5") (pin "11") (pinfunction "11_11") (pintype "passive"))
      (node (ref "R2") (pin "1") (pinfunction "1_1") (pintype "passive"))
    )
    (net (code "64") (name "WT_IN") (class "Default")
      (node (ref "R6") (pin "2") (pinfunction "2_2") (pintype "passive"))
      (node (ref "U1") (pin "1") (pinfunction "ANODE1_1") (pintype "input"))
    )
    (net (code "65") (name "WT_INV") (class "Default")
      (node (ref "R7") (pin "1") (pinfunction "1_1") (pintype "passive"))
      (node (ref "U1") (pin "7") (pinfunction "VOUT1_7") (pintype "output"))
      (node (ref "U3") (pin "P2") (pinfunction "A_P2") (pintype "input"))
    )
    (net (code "66") (name "WT_OUT") (class "Default")
      (node (ref "R10") (pin "P5") (pinfunction "2_P5") (pintype "passive"))
      (node (ref "U3") (pin "P4") (pinfunction "Y_P4") (pintype "output"))
    )
    (net (code "67") (name "unconnected-(J7-Pad1)") (class "Default")
      (node (ref "J7") (pin "1") (pinfunction "1_1") (pintype "passive"))
    )
    (net (code "68") (name "unconnected-(J7-Pad4)") (class "Default")
      (node (ref "J7") (pin "4") (pinfunction "4_4") (pintype "passive"))
    )
    (net (code "69") (name "unconnected-(J7-Pad5)") (class "Default")
      (node (ref "J7") (pin "5") (pinfunction "5_5") (pintype "passive"))
    )
    (net (code "70") (name "unconnected-(U2-ANT_DETECT-PadP4)") (class "Default")
      (node (ref "U2") (pin "P4") (pinfunction "ANT_DETECT_P4") (pintype "input"))
    )
    (net (code "71") (name "unconnected-(U2-ANT_OFF-PadP5)") (class "Default")
      (node (ref "U2") (pin "P5") (pinfunction "ANT_OFF_P5") (pintype "output"))
    )
    (net (code "72") (name "unconnected-(U2-RSVD-PadP8)") (class "Default")
      (node (ref "U2") (pin "P8") (pinfunction "RSVD_P8") (pintype "no_connect"))
    )
    (net (code "73") (name "unconnected-(U2-RSVD-PadP9)") (class "Default")
      (node (ref "U2") (pin "P9") (pinfunction "RSVD_P9") (pintype "no_connect"))
    )
    (net (code "74") (name "unconnected-(U2-RSVD-PadP10)") (class "Default")
      (node (ref "U2") (pin "P10") (pinfunction "RSVD_P10") (pintype "no_connect"))
    )
    (net (code "75") (name "unconnected-(U2-RSVD-PadP11)") (class "Default")
      (node (ref "U2") (pin "P11") (pinfunction "RSVD_P11") (pintype "no_connect"))
    )
    (net (code "76") (name "unconnected-(U2-RSVD-PadP13)") (class "Default")
      (node (ref "U2") (pin "P13") (pinfunction "RSVD_P13") (pintype "no_connect"))
    )
    (net (code "77") (name "unconnected-(U2-RSVD-PadP15)") (class "Default")
      (node (ref "U2") (pin "P15") (pinfunction "RSVD_P15") (pintype "no_connect"))
    )
    (net (code "78") (name "unconnected-(U2-RSVD-PadP16)") (class "Default")
      (node (ref "U2") (pin "P16") (pinfunction "RSVD_P16") (pintype "no_connect"))
    )
    (net (code "79") (name "unconnected-(U2-RSVD-PadP17)") (class "Default")
      (node (ref "U2") (pin "P17") (pinfunction "RSVD_P17") (pintype "no_connect"))
    )
    (net (code "80") (name "unconnected-(U2-RSVD-PadP18)") (class "Default")
      (node (ref "U2") (pin "P18") (pinfunction "RSVD_P18") (pintype "no_connect"))
    )
    (net (code "81") (name "unconnected-(U2-RSVD-PadP21)") (class "Default")
      (node (ref "U2") (pin "P21") (pinfunction "RSVD_P21") (pintype "no_connect"))
    )
    (net (code "82") (name "unconnected-(U2-RSVD-PadP24)") (class "Default")
      (node (ref "U2") (pin "P24") (pinfunction "RSVD_P24") (pintype "no_connect"))
    )
    (net (code "83") (name "unconnected-(U2-RSVD-PadP25)") (class "Default")
      (node (ref "U2") (pin "P25") (pinfunction "RSVD_P25") (pintype "no_connect"))
    )
    (net (code "84") (name "unconnected-(U2-RSVD-PadP28)") (class "Default")
      (node (ref "U2") (pin "P28") (pinfunction "RSVD_P28") (pintype "no_connect"))
    )
    (net (code "85") (name "unconnected-(U2-RSVD-PadP29)") (class "Default")
      (node (ref "U2") (pin "P29") (pinfunction "RSVD_P29") (pintype "no_connect"))
    )
    (net (code "86") (name "unconnected-(U2-RSVD-PadP30)") (class "Default")
      (node (ref "U2") (pin "P30") (pinfunction "RSVD_P30") (pintype "no_connect"))
    )
    (net (code "87") (name "unconnected-(U2-RSVD-PadP31)") (class "Default")
      (node (ref "U2") (pin "P31") (pinfunction "RSVD_P31") (pintype "no_connect"))
    )
    (net (code "88") (name "unconnected-(U2-RSVD-PadP35)") (class "Default")
      (node (ref "U2") (pin "P35") (pinfunction "RSVD_P35") (pintype "no_connect"))
    )
    (net (code "89") (name "unconnected-(U2-RSVD-PadP52)") (class "Default")
      (node (ref "U2") (pin "P52") (pinfunction "RSVD_P52") (pintype "no_connect"))
    )
    (net (code "90") (name "unconnected-(U2-RSVD-PadP54)") (class "Default")
      (node (ref "U2") (pin "P54") (pinfunction "RSVD_P54") (pintype "no_connect"))
    )
    (net (code "91") (name "unconnected-(U2-~{ANT_SHORT}-PadP6)") (class "Default")
      (node (ref "U2") (pin "P6") (pinfunction "~{ANT_SHORT}_P6") (pintype "output"))
    )
    (net (code "92") (name "unconnected-(U5-NC-Pad4)") (class "Default")
      (node (ref "U5") (pin "4") (pinfunction "NC_4") (pintype "no_connect"))
    )
  )
)
